# 2_Cart__schdoc.net
KiCad netlist of a schematic drawn in Altium Designer
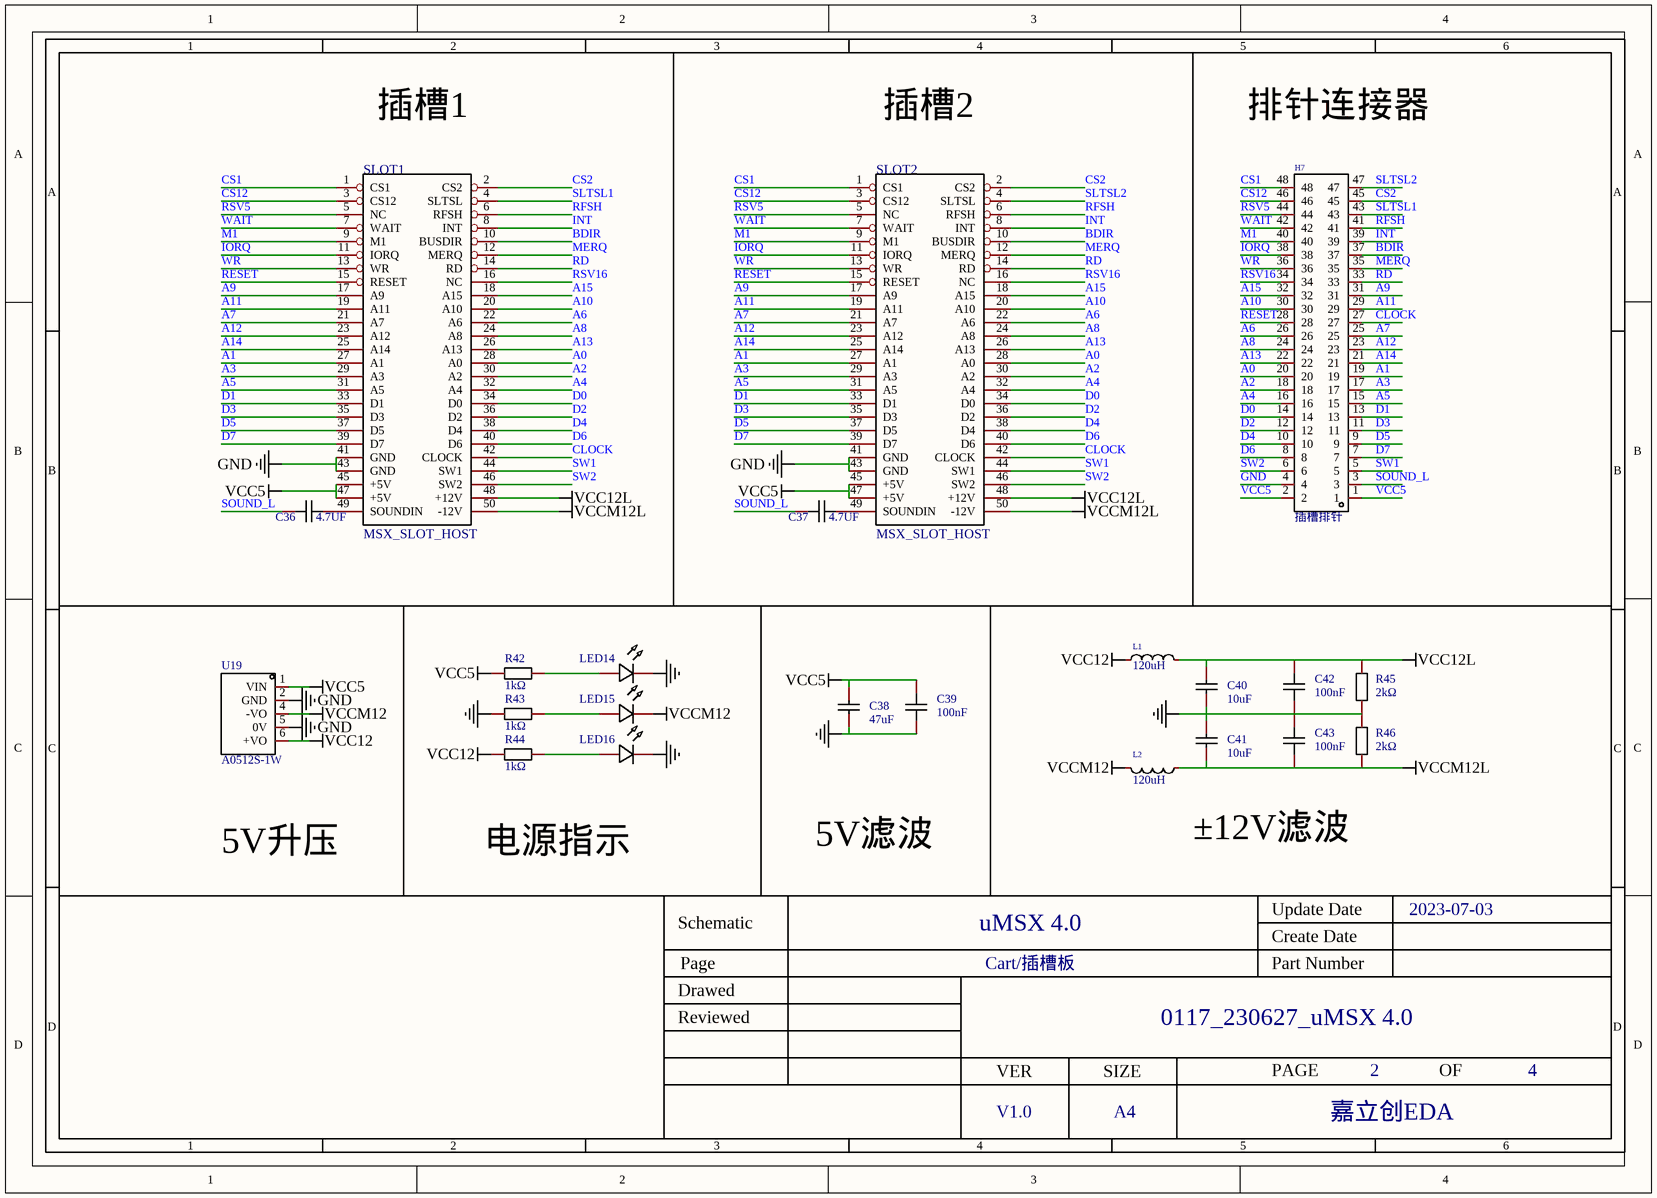
[diagram p0: 2_Cart_插槽板.schdoc.schdoc]

(export (version "E")
  (design (tool "Eeschema 10.0.6"))
  (components
    (comp (ref "C36")
      (value "4.7UF")
      (fields (field (name "NAME") "4.7UF"))
      (libsource (lib "altium-import") (part "root_0_CAP_0603_"))
    )
    (comp (ref "C37")
      (value "4.7UF")
      (fields (field (name "NAME") "4.7UF"))
      (libsource (lib "altium-import") (part "root_0_CAP_0603_"))
    )
    (comp (ref "C38")
      (value "47uF")
      (fields
        (field (name "NAME") "47uF")
        (field (name "MANUFACTURER") "SAMSUNG(三星)")
        (field (name "MANUFACTURER PART") "CL21A476MQYNNNE")
        (field (name "TOLERANCE") "±20%")
      )
      (libsource (lib "altium-import") (part "root_1_CL21A476MQYNNNE_"))
    )
    (comp (ref "C39")
      (value "100nF")
      (fields (field (name "NAME") "100nF"))
      (libsource (lib "altium-import") (part "root_1_CAP_0603_"))
    )
    (comp (ref "C40")
      (value "10uF")
      (fields
        (field (name "NAME") "10uF")
        (field (name "MANUFACTURER") "SAMSUNG(三星)")
        (field (name "MANUFACTURER PART") "CL21A476MQYNNNE")
        (field (name "TOLERANCE") "±20%")
      )
      (libsource (lib "altium-import") (part "root_1_CL21A476MQYNNNE_"))
    )
    (comp (ref "C41")
      (value "10uF")
      (fields
        (field (name "NAME") "10uF")
        (field (name "MANUFACTURER") "SAMSUNG(三星)")
        (field (name "MANUFACTURER PART") "CL21A476MQYNNNE")
        (field (name "TOLERANCE") "±20%")
      )
      (libsource (lib "altium-import") (part "root_1_CL21A476MQYNNNE_"))
    )
    (comp (ref "C42")
      (value "100nF")
      (fields (field (name "NAME") "100nF"))
      (libsource (lib "altium-import") (part "root_1_CAP_0603_"))
    )
    (comp (ref "C43")
      (value "100nF")
      (fields (field (name "NAME") "100nF"))
      (libsource (lib "altium-import") (part "root_3_mirrored_CAP_0603_"))
    )
    (comp (ref "H7")
      (value "插槽排针")
      (fields (field (name "NAME") "插槽排针") (field (name "MANUFACTURER") "XKB Connectivity(中国星坤)"))
      (libsource (lib "altium-import") (part "root_2_X6521WR-2x24H-C30D60_"))
    )
    (comp (ref "L1")
      (value "120uH")
      (fields
        (field (name "NAME") "120uH")
        (field (name "MANUFACTURER") "增益")
        (field (name "MANUFACTURER PART") "A-6-9007-2")
        (field (name "TOLERANCE") "±25%")
      )
      (libsource (lib "altium-import") (part "root_0_A-6-9007-2_"))
    )
    (comp (ref "L2")
      (value "120uH")
      (fields
        (field (name "NAME") "120uH")
        (field (name "MANUFACTURER") "增益")
        (field (name "MANUFACTURER PART") "A-6-9007-2")
        (field (name "TOLERANCE") "±25%")
      )
      (libsource (lib "altium-import") (part "root_2_mirrored_A-6-9007-2_"))
    )
    (comp (ref "LED14") (value "LED_0603-R") (libsource (lib "altium-import") (part "root_0_LED_0603-R_")))
    (comp (ref "LED15") (value "LED_0603-R") (libsource (lib "altium-import") (part "root_0_LED_0603-R_")))
    (comp (ref "LED16") (value "LED_0603-R") (libsource (lib "altium-import") (part "root_0_LED_0603-R_")))
    (comp (ref "R42")
      (value "1kΩ")
      (fields
        (field (name "NAME") "1kΩ")
        (field (name "MANUFACTURER") "UNI-ROYAL(厚声)")
        (field (name "MANUFACTURER PART") "0603WAF1001T5E")
        (field (name "TOLERANCE") "±1%")
      )
      (libsource (lib "altium-import") (part "root_0_0603WAF1001T5E_"))
    )
    (comp (ref "R43")
      (value "1kΩ")
      (fields
        (field (name "NAME") "1kΩ")
        (field (name "MANUFACTURER") "UNI-ROYAL(厚声)")
        (field (name "MANUFACTURER PART") "0603WAF1001T5E")
        (field (name "TOLERANCE") "±1%")
      )
      (libsource (lib "altium-import") (part "root_0_0603WAF1001T5E_"))
    )
    (comp (ref "R44")
      (value "1kΩ")
      (fields
        (field (name "NAME") "1kΩ")
        (field (name "MANUFACTURER") "UNI-ROYAL(厚声)")
        (field (name "MANUFACTURER PART") "0603WAF1001T5E")
        (field (name "TOLERANCE") "±1%")
      )
      (libsource (lib "altium-import") (part "root_0_0603WAF1001T5E_"))
    )
    (comp (ref "R45")
      (value "2kΩ")
      (fields
        (field (name "NAME") "2kΩ")
        (field (name "MANUFACTURER") "UNI-ROYAL(厚声)")
        (field (name "MANUFACTURER PART") "0603WAF2001T5E")
        (field (name "TOLERANCE") "±1%")
      )
      (libsource (lib "altium-import") (part "root_1_0603WAF2001T5E_"))
    )
    (comp (ref "R46")
      (value "2kΩ")
      (fields
        (field (name "NAME") "2kΩ")
        (field (name "MANUFACTURER") "UNI-ROYAL(厚声)")
        (field (name "MANUFACTURER PART") "0603WAF2001T5E")
        (field (name "TOLERANCE") "±1%")
      )
      (libsource (lib "altium-import") (part "root_3_mirrored_0603WAF2001T5E_"))
    )
    (comp (ref "SLOT1")
      (value "MSX_SLOT_HOST")
      (fields (field (name "NAME") "MSX_SLOT_HOST"))
      (libsource (lib "altium-import") (part "root_0_MSX_SLOT_HOST_"))
    )
    (comp (ref "SLOT2")
      (value "MSX_SLOT_HOST")
      (fields (field (name "NAME") "MSX_SLOT_HOST"))
      (libsource (lib "altium-import") (part "root_0_MSX_SLOT_HOST_"))
    )
    (comp (ref "U19")
      (value "A0512S-1W")
      (fields (field (name "NAME") "A0512S-1W") (field (name "MANUFACTURER") "HENIPER(恒浦)"))
      (libsource (lib "altium-import") (part "root_0_mirrored_A0512S-1W_"))
    )
  )
  (nets
    (net (code "1") (name "/A0") (class "Default")
      (node (ref "H7") (pin "20") (pinfunction "20_20") (pintype "passive"))
      (node (ref "SLOT1") (pin "28") (pinfunction "A0_28") (pintype "passive"))
      (node (ref "SLOT2") (pin "28") (pinfunction "A0_28") (pintype "passive"))
    )
    (net (code "2") (name "/A1") (class "Default")
      (node (ref "H7") (pin "19") (pinfunction "19_19") (pintype "passive"))
      (node (ref "SLOT1") (pin "27") (pinfunction "A1_27") (pintype "passive"))
      (node (ref "SLOT2") (pin "27") (pinfunction "A1_27") (pintype "passive"))
    )
    (net (code "3") (name "/A2") (class "Default")
      (node (ref "H7") (pin "18") (pinfunction "18_18") (pintype "passive"))
      (node (ref "SLOT1") (pin "30") (pinfunction "A2_30") (pintype "passive"))
      (node (ref "SLOT2") (pin "30") (pinfunction "A2_30") (pintype "passive"))
    )
    (net (code "4") (name "/A3") (class "Default")
      (node (ref "H7") (pin "17") (pinfunction "17_17") (pintype "passive"))
      (node (ref "SLOT1") (pin "29") (pinfunction "A3_29") (pintype "passive"))
      (node (ref "SLOT2") (pin "29") (pinfunction "A3_29") (pintype "passive"))
    )
    (net (code "5") (name "/A4") (class "Default")
      (node (ref "H7") (pin "16") (pinfunction "16_16") (pintype "passive"))
      (node (ref "SLOT1") (pin "32") (pinfunction "A4_32") (pintype "passive"))
      (node (ref "SLOT2") (pin "32") (pinfunction "A4_32") (pintype "passive"))
    )
    (net (code "6") (name "/A5") (class "Default")
      (node (ref "H7") (pin "15") (pinfunction "15_15") (pintype "passive"))
      (node (ref "SLOT1") (pin "31") (pinfunction "A5_31") (pintype "passive"))
      (node (ref "SLOT2") (pin "31") (pinfunction "A5_31") (pintype "passive"))
    )
    (net (code "7") (name "/A6") (class "Default")
      (node (ref "H7") (pin "26") (pinfunction "26_26") (pintype "passive"))
      (node (ref "SLOT1") (pin "22") (pinfunction "A6_22") (pintype "passive"))
      (node (ref "SLOT2") (pin "22") (pinfunction "A6_22") (pintype "passive"))
    )
    (net (code "8") (name "/A7") (class "Default")
      (node (ref "H7") (pin "25") (pinfunction "25_25") (pintype "passive"))
      (node (ref "SLOT1") (pin "21") (pinfunction "A7_21") (pintype "passive"))
      (node (ref "SLOT2") (pin "21") (pinfunction "A7_21") (pintype "passive"))
    )
    (net (code "9") (name "/A8") (class "Default")
      (node (ref "H7") (pin "24") (pinfunction "24_24") (pintype "passive"))
      (node (ref "SLOT1") (pin "24") (pinfunction "A8_24") (pintype "passive"))
      (node (ref "SLOT2") (pin "24") (pinfunction "A8_24") (pintype "passive"))
    )
    (net (code "10") (name "/A9") (class "Default")
      (node (ref "H7") (pin "31") (pinfunction "31_31") (pintype "passive"))
      (node (ref "SLOT1") (pin "17") (pinfunction "A9_17") (pintype "passive"))
      (node (ref "SLOT2") (pin "17") (pinfunction "A9_17") (pintype "passive"))
    )
    (net (code "11") (name "/A10") (class "Default")
      (node (ref "H7") (pin "30") (pinfunction "30_30") (pintype "passive"))
      (node (ref "SLOT1") (pin "20") (pinfunction "A10_20") (pintype "passive"))
      (node (ref "SLOT2") (pin "20") (pinfunction "A10_20") (pintype "passive"))
    )
    (net (code "12") (name "/A11") (class "Default")
      (node (ref "H7") (pin "29") (pinfunction "29_29") (pintype "passive"))
      (node (ref "SLOT1") (pin "19") (pinfunction "A11_19") (pintype "passive"))
      (node (ref "SLOT2") (pin "19") (pinfunction "A11_19") (pintype "passive"))
    )
    (net (code "13") (name "/A12") (class "Default")
      (node (ref "H7") (pin "23") (pinfunction "23_23") (pintype "passive"))
      (node (ref "SLOT1") (pin "23") (pinfunction "A12_23") (pintype "passive"))
      (node (ref "SLOT2") (pin "23") (pinfunction "A12_23") (pintype "passive"))
    )
    (net (code "14") (name "/A13") (class "Default")
      (node (ref "H7") (pin "22") (pinfunction "22_22") (pintype "passive"))
      (node (ref "SLOT1") (pin "26") (pinfunction "A13_26") (pintype "passive"))
      (node (ref "SLOT2") (pin "26") (pinfunction "A13_26") (pintype "passive"))
    )
    (net (code "15") (name "/A14") (class "Default")
      (node (ref "H7") (pin "21") (pinfunction "21_21") (pintype "passive"))
      (node (ref "SLOT1") (pin "25") (pinfunction "A14_25") (pintype "passive"))
      (node (ref "SLOT2") (pin "25") (pinfunction "A14_25") (pintype "passive"))
    )
    (net (code "16") (name "/A15") (class "Default")
      (node (ref "H7") (pin "32") (pinfunction "32_32") (pintype "passive"))
      (node (ref "SLOT1") (pin "18") (pinfunction "A15_18") (pintype "passive"))
      (node (ref "SLOT2") (pin "18") (pinfunction "A15_18") (pintype "passive"))
    )
    (net (code "17") (name "/BDIR") (class "Default")
      (node (ref "H7") (pin "37") (pinfunction "37_37") (pintype "passive"))
      (node (ref "SLOT1") (pin "10") (pinfunction "BUSDIR_10") (pintype "passive"))
      (node (ref "SLOT2") (pin "10") (pinfunction "BUSDIR_10") (pintype "passive"))
    )
    (net (code "18") (name "/CLOCK") (class "Default")
      (node (ref "H7") (pin "27") (pinfunction "27_27") (pintype "passive"))
      (node (ref "SLOT1") (pin "42") (pinfunction "CLOCK_42") (pintype "passive"))
      (node (ref "SLOT2") (pin "42") (pinfunction "CLOCK_42") (pintype "passive"))
    )
    (net (code "19") (name "/CS1") (class "Default")
      (node (ref "H7") (pin "48") (pinfunction "48_48") (pintype "passive"))
      (node (ref "SLOT1") (pin "1") (pinfunction "CS1_1") (pintype "passive"))
      (node (ref "SLOT2") (pin "1") (pinfunction "CS1_1") (pintype "passive"))
    )
    (net (code "20") (name "/CS2") (class "Default")
      (node (ref "H7") (pin "45") (pinfunction "45_45") (pintype "passive"))
      (node (ref "SLOT1") (pin "2") (pinfunction "CS2_2") (pintype "passive"))
      (node (ref "SLOT2") (pin "2") (pinfunction "CS2_2") (pintype "passive"))
    )
    (net (code "21") (name "/CS12") (class "Default")
      (node (ref "H7") (pin "46") (pinfunction "46_46") (pintype "passive"))
      (node (ref "SLOT1") (pin "3") (pinfunction "CS12_3") (pintype "passive"))
      (node (ref "SLOT2") (pin "3") (pinfunction "CS12_3") (pintype "passive"))
    )
    (net (code "22") (name "/D0") (class "Default")
      (node (ref "H7") (pin "14") (pinfunction "14_14") (pintype "passive"))
      (node (ref "SLOT1") (pin "34") (pinfunction "D0_34") (pintype "passive"))
      (node (ref "SLOT2") (pin "34") (pinfunction "D0_34") (pintype "passive"))
    )
    (net (code "23") (name "/D1") (class "Default")
      (node (ref "H7") (pin "13") (pinfunction "13_13") (pintype "passive"))
      (node (ref "SLOT1") (pin "33") (pinfunction "D1_33") (pintype "passive"))
      (node (ref "SLOT2") (pin "33") (pinfunction "D1_33") (pintype "passive"))
    )
    (net (code "24") (name "/D2") (class "Default")
      (node (ref "H7") (pin "12") (pinfunction "12_12") (pintype "passive"))
      (node (ref "SLOT1") (pin "36") (pinfunction "D2_36") (pintype "passive"))
      (node (ref "SLOT2") (pin "36") (pinfunction "D2_36") (pintype "passive"))
    )
    (net (code "25") (name "/D3") (class "Default")
      (node (ref "H7") (pin "11") (pinfunction "11_11") (pintype "passive"))
      (node (ref "SLOT1") (pin "35") (pinfunction "D3_35") (pintype "passive"))
      (node (ref "SLOT2") (pin "35") (pinfunction "D3_35") (pintype "passive"))
    )
    (net (code "26") (name "/D4") (class "Default")
      (node (ref "H7") (pin "10") (pinfunction "10_10") (pintype "passive"))
      (node (ref "SLOT1") (pin "38") (pinfunction "D4_38") (pintype "passive"))
      (node (ref "SLOT2") (pin "38") (pinfunction "D4_38") (pintype "passive"))
    )
    (net (code "27") (name "/D5") (class "Default")
      (node (ref "H7") (pin "9") (pinfunction "9_9") (pintype "passive"))
      (node (ref "SLOT1") (pin "37") (pinfunction "D5_37") (pintype "passive"))
      (node (ref "SLOT2") (pin "37") (pinfunction "D5_37") (pintype "passive"))
    )
    (net (code "28") (name "/D6") (class "Default")
      (node (ref "H7") (pin "8") (pinfunction "8_8") (pintype "passive"))
      (node (ref "SLOT1") (pin "40") (pinfunction "D6_40") (pintype "passive"))
      (node (ref "SLOT2") (pin "40") (pinfunction "D6_40") (pintype "passive"))
    )
    (net (code "29") (name "/D7") (class "Default")
      (node (ref "H7") (pin "7") (pinfunction "7_7") (pintype "passive"))
      (node (ref "SLOT1") (pin "39") (pinfunction "D7_39") (pintype "passive"))
      (node (ref "SLOT2") (pin "39") (pinfunction "D7_39") (pintype "passive"))
    )
    (net (code "30") (name "/INT") (class "Default")
      (node (ref "H7") (pin "39") (pinfunction "39_39") (pintype "passive"))
      (node (ref "SLOT1") (pin "8") (pinfunction "INT_8") (pintype "passive"))
      (node (ref "SLOT2") (pin "8") (pinfunction "INT_8") (pintype "passive"))
    )
    (net (code "31") (name "/IORQ") (class "Default")
      (node (ref "H7") (pin "38") (pinfunction "38_38") (pintype "passive"))
      (node (ref "SLOT1") (pin "11") (pinfunction "IORQ_11") (pintype "passive"))
      (node (ref "SLOT2") (pin "11") (pinfunction "IORQ_11") (pintype "passive"))
    )
    (net (code "32") (name "/M1") (class "Default")
      (node (ref "H7") (pin "40") (pinfunction "40_40") (pintype "passive"))
      (node (ref "SLOT1") (pin "9") (pinfunction "M1_9") (pintype "passive"))
      (node (ref "SLOT2") (pin "9") (pinfunction "M1_9") (pintype "passive"))
    )
    (net (code "33") (name "/MERQ") (class "Default")
      (node (ref "H7") (pin "35") (pinfunction "35_35") (pintype "passive"))
      (node (ref "SLOT1") (pin "12") (pinfunction "MERQ_12") (pintype "passive"))
      (node (ref "SLOT2") (pin "12") (pinfunction "MERQ_12") (pintype "passive"))
    )
    (net (code "34") (name "/RD") (class "Default")
      (node (ref "H7") (pin "33") (pinfunction "33_33") (pintype "passive"))
      (node (ref "SLOT1") (pin "14") (pinfunction "RD_14") (pintype "passive"))
      (node (ref "SLOT2") (pin "14") (pinfunction "RD_14") (pintype "passive"))
    )
    (net (code "35") (name "/RESET") (class "Default")
      (node (ref "H7") (pin "28") (pinfunction "28_28") (pintype "passive"))
      (node (ref "SLOT1") (pin "15") (pinfunction "RESET_15") (pintype "passive"))
      (node (ref "SLOT2") (pin "15") (pinfunction "RESET_15") (pintype "passive"))
    )
    (net (code "36") (name "/RFSH") (class "Default")
      (node (ref "H7") (pin "41") (pinfunction "41_41") (pintype "passive"))
      (node (ref "SLOT1") (pin "6") (pinfunction "RFSH_6") (pintype "passive"))
      (node (ref "SLOT2") (pin "6") (pinfunction "RFSH_6") (pintype "passive"))
    )
    (net (code "37") (name "/RSV5") (class "Default")
      (node (ref "H7") (pin "44") (pinfunction "44_44") (pintype "passive"))
      (node (ref "SLOT1") (pin "5") (pinfunction "NC_5") (pintype "passive"))
      (node (ref "SLOT2") (pin "5") (pinfunction "NC_5") (pintype "passive"))
    )
    (net (code "38") (name "/RSV16") (class "Default")
      (node (ref "H7") (pin "34") (pinfunction "34_34") (pintype "passive"))
      (node (ref "SLOT1") (pin "16") (pinfunction "NC_16") (pintype "passive"))
      (node (ref "SLOT2") (pin "16") (pinfunction "NC_16") (pintype "passive"))
    )
    (net (code "39") (name "/SLTSL1") (class "Default")
      (node (ref "H7") (pin "43") (pinfunction "43_43") (pintype "passive"))
      (node (ref "SLOT1") (pin "4") (pinfunction "SLTSL_4") (pintype "passive"))
    )
    (net (code "40") (name "/SLTSL2") (class "Default")
      (node (ref "H7") (pin "47") (pinfunction "47_47") (pintype "passive"))
      (node (ref "SLOT2") (pin "4") (pinfunction "SLTSL_4") (pintype "passive"))
    )
    (net (code "41") (name "/SOUND_L") (class "Default")
      (node (ref "C36") (pin "1") (pinfunction "1_1") (pintype "passive"))
      (node (ref "C37") (pin "1") (pinfunction "1_1") (pintype "passive"))
      (node (ref "H7") (pin "3") (pinfunction "3_3") (pintype "passive"))
    )
    (net (code "42") (name "/SW1") (class "Default")
      (node (ref "H7") (pin "5") (pinfunction "5_5") (pintype "passive"))
      (node (ref "SLOT1") (pin "44") (pinfunction "SW1_44") (pintype "passive"))
      (node (ref "SLOT2") (pin "44") (pinfunction "SW1_44") (pintype "passive"))
    )
    (net (code "43") (name "/SW2") (class "Default")
      (node (ref "H7") (pin "6") (pinfunction "6_6") (pintype "passive"))
      (node (ref "SLOT1") (pin "46") (pinfunction "SW2_46") (pintype "passive"))
      (node (ref "SLOT2") (pin "46") (pinfunction "SW2_46") (pintype "passive"))
    )
    (net (code "44") (name "/WAIT") (class "Default")
      (node (ref "H7") (pin "42") (pinfunction "42_42") (pintype "passive"))
      (node (ref "SLOT1") (pin "7") (pinfunction "WAIT_7") (pintype "passive"))
      (node (ref "SLOT2") (pin "7") (pinfunction "WAIT_7") (pintype "passive"))
    )
    (net (code "45") (name "/WR") (class "Default")
      (node (ref "H7") (pin "36") (pinfunction "36_36") (pintype "passive"))
      (node (ref "SLOT1") (pin "13") (pinfunction "WR_13") (pintype "passive"))
      (node (ref "SLOT2") (pin "13") (pinfunction "WR_13") (pintype "passive"))
    )
    (net (code "46") (name "<NO NET>") (class "Default")
      (node (ref "C38") (pin "1") (pinfunction "1_1") (pintype "passive"))
      (node (ref "C39") (pin "1") (pinfunction "1_1") (pintype "passive"))
      (node (ref "C40") (pin "1") (pinfunction "1_1") (pintype "passive"))
      (node (ref "C41") (pin "2") (pinfunction "2_2") (pintype "passive"))
      (node (ref "C42") (pin "1") (pinfunction "1_1") (pintype "passive"))
      (node (ref "C43") (pin "1") (pinfunction "1_1") (pintype "passive"))
      (node (ref "LED14") (pin "1") (pinfunction "C_1") (pintype "passive"))
      (node (ref "LED16") (pin "1") (pinfunction "C_1") (pintype "passive"))
      (node (ref "R43") (pin "1") (pinfunction "1_1") (pintype "passive"))
      (node (ref "R45") (pin "1") (pinfunction "1_1") (pintype "passive"))
      (node (ref "R46") (pin "1") (pinfunction "1_1") (pintype "passive"))
    )
    (net (code "47") (name "GND") (class "Default")
      (node (ref "H7") (pin "4") (pinfunction "4_4") (pintype "passive"))
      (node (ref "SLOT1") (pin "41") (pinfunction "GND_41") (pintype "passive"))
      (node (ref "SLOT1") (pin "43") (pinfunction "GND_43") (pintype "passive"))
      (node (ref "SLOT2") (pin "41") (pinfunction "GND_41") (pintype "passive"))
      (node (ref "SLOT2") (pin "43") (pinfunction "GND_43") (pintype "passive"))
      (node (ref "U19") (pin "2") (pinfunction "GND_2") (pintype "passive"))
      (node (ref "U19") (pin "5") (pinfunction "0V_5") (pintype "passive"))
    )
    (net (code "48") (name "Net-(LED14-A)") (class "Default")
      (node (ref "LED14") (pin "2") (pinfunction "A_2") (pintype "passive"))
      (node (ref "R42") (pin "2") (pinfunction "2_2") (pintype "passive"))
    )
    (net (code "49") (name "Net-(LED15-A)") (class "Default")
      (node (ref "LED15") (pin "2") (pinfunction "A_2") (pintype "passive"))
      (node (ref "R43") (pin "2") (pinfunction "2_2") (pintype "passive"))
    )
    (net (code "50") (name "Net-(LED16-A)") (class "Default")
      (node (ref "LED16") (pin "2") (pinfunction "A_2") (pintype "passive"))
      (node (ref "R44") (pin "2") (pinfunction "2_2") (pintype "passive"))
    )
    (net (code "51") (name "Net-(SLOT1-SOUNDIN)") (class "Default")
      (node (ref "C36") (pin "2") (pinfunction "2_2") (pintype "passive"))
      (node (ref "SLOT1") (pin "49") (pinfunction "SOUNDIN_49") (pintype "passive"))
    )
    (net (code "52") (name "Net-(SLOT2-SOUNDIN)") (class "Default")
      (node (ref "C37") (pin "2") (pinfunction "2_2") (pintype "passive"))
      (node (ref "SLOT2") (pin "49") (pinfunction "SOUNDIN_49") (pintype "passive"))
    )
    (net (code "53") (name "VCC5") (class "Default")
      (node (ref "C38") (pin "2") (pinfunction "2_2") (pintype "passive"))
      (node (ref "C39") (pin "2") (pinfunction "2_2") (pintype "passive"))
      (node (ref "H7") (pin "1") (pinfunction "1_1") (pintype "passive"))
      (node (ref "H7") (pin "2") (pinfunction "2_2") (pintype "passive"))
      (node (ref "R42") (pin "1") (pinfunction "1_1") (pintype "passive"))
      (node (ref "SLOT1") (pin "45") (pinfunction "+5V_45") (pintype "passive"))
      (node (ref "SLOT1") (pin "47") (pinfunction "+5V_47") (pintype "passive"))
      (node (ref "SLOT2") (pin "45") (pinfunction "+5V_45") (pintype "passive"))
      (node (ref "SLOT2") (pin "47") (pinfunction "+5V_47") (pintype "passive"))
      (node (ref "U19") (pin "1") (pinfunction "VIN_1") (pintype "passive"))
    )
    (net (code "54") (name "VCC12") (class "Default")
      (node (ref "L1") (pin "1") (pinfunction "1_1") (pintype "passive"))
      (node (ref "R44") (pin "1") (pinfunction "1_1") (pintype "passive"))
      (node (ref "U19") (pin "6") (pinfunction "+VO_6") (pintype "passive"))
    )
    (net (code "55") (name "VCC12L") (class "Default")
      (node (ref "C40") (pin "2") (pinfunction "2_2") (pintype "passive"))
      (node (ref "C42") (pin "2") (pinfunction "2_2") (pintype "passive"))
      (node (ref "L1") (pin "2") (pinfunction "2_2") (pintype "passive"))
      (node (ref "R45") (pin "2") (pinfunction "2_2") (pintype "passive"))
      (node (ref "SLOT1") (pin "48") (pinfunction "+12V_48") (pintype "passive"))
      (node (ref "SLOT2") (pin "48") (pinfunction "+12V_48") (pintype "passive"))
    )
    (net (code "56") (name "VCCM12") (class "Default")
      (node (ref "L2") (pin "1") (pinfunction "1_1") (pintype "passive"))
      (node (ref "LED15") (pin "1") (pinfunction "C_1") (pintype "passive"))
      (node (ref "U19") (pin "4") (pinfunction "-VO_4") (pintype "passive"))
    )
    (net (code "57") (name "VCCM12L") (class "Default")
      (node (ref "C41") (pin "1") (pinfunction "1_1") (pintype "passive"))
      (node (ref "C43") (pin "2") (pinfunction "2_2") (pintype "passive"))
      (node (ref "L2") (pin "2") (pinfunction "2_2") (pintype "passive"))
      (node (ref "R46") (pin "2") (pinfunction "2_2") (pintype "passive"))
      (node (ref "SLOT1") (pin "50") (pinfunction "-12V_50") (pintype "passive"))
      (node (ref "SLOT2") (pin "50") (pinfunction "-12V_50") (pintype "passive"))
    )
  )
)
